# Sheet1.net
KiCad netlist of a schematic drawn in Altium Designer
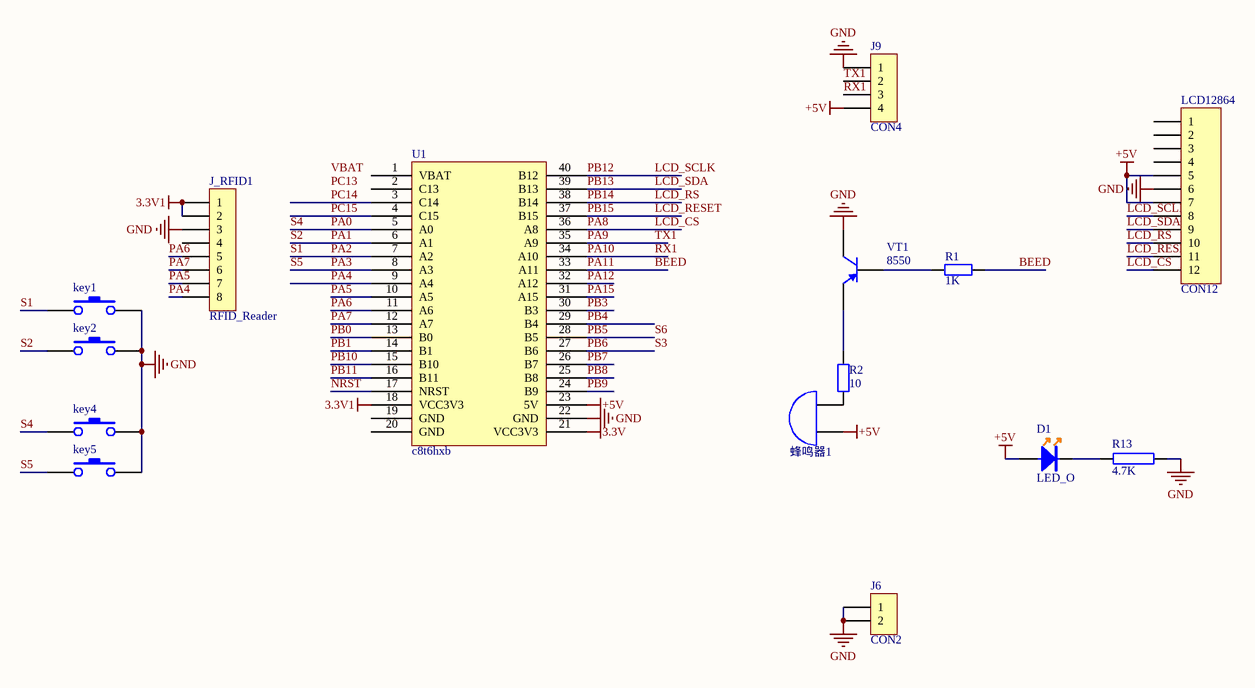
[diagram p0: Sheet1.SchDoc]

(export (version "E")
  (design (tool "Eeschema 10.0.6"))
  (components
    (comp (ref "D1") (value "LED_O") (footprint "D0805") (libsource (lib "Diode二极管") (part "LED_O")))
    (comp (ref "J6")
      (value "CON2")
      (footprint "sip-2")
      (description "Connector")
      (libsource (lib "接口") (part "CON2"))
    )
    (comp (ref "J9")
      (value "CON4")
      (footprint "sip-4")
      (description "Connector")
      (libsource (lib "接口") (part "CON4"))
    )
    (comp (ref "J_RFID1")
      (value "RFID_Reader")
      (footprint "SIP-8")
      (description "Connector")
      (libsource (lib "Plugs插头") (part "CON8"))
    )
    (comp (ref "key1") (value "~") (footprint "SW_SMD_P2") (libsource (lib "Switch开关") (part "SW-PB")))
    (comp (ref "key2") (value "~") (footprint "SW_SMD_P2") (libsource (lib "Switch开关") (part "SW-PB")))
    (comp (ref "key4") (value "~") (footprint "SW_SMD_P2") (libsource (lib "Switch开关") (part "SW-PB")))
    (comp (ref "key5") (value "~") (footprint "SW_SMD_P2") (libsource (lib "Switch开关") (part "SW-PB")))
    (comp (ref "LCD12864")
      (value "CON12")
      (footprint "sip-12")
      (description "Connector")
      (libsource (lib "接口") (part "CON12"))
    )
    (comp (ref "R1")
      (value "1K")
      (footprint "0805")
      (fields (field (name "Comment") "Res"))
      (libsource (lib "") (part "Res_1"))
    )
    (comp (ref "R2")
      (value "10")
      (footprint "0805")
      (fields (field (name "Comment") "Res"))
      (libsource (lib "MY") (part "Res"))
    )
    (comp (ref "R13") (value "4.7K") (footprint "0805") (libsource (lib "Resistance电阻") (part "RES")))
    (comp (ref "U1") (value "c8t6hxb") (footprint "48P") (libsource (lib "STM32F103C8T6") (part "c8t6hxb")))
    (comp (ref "VT1") (value "8550") (footprint "SOT-23") (libsource (lib "MY") (part "8550")))
    (comp (ref "蜂鸣器1") (value "蜂鸣器") (footprint "DB") (libsource (lib "MY") (part "蜂鸣器")))
  )
  (nets
    (net (code "1") (name "+5V") (class "Default")
      (node (ref "D1") (pin "1") (pinfunction "1_1") (pintype "passive"))
      (node (ref "J9") (pin "4") (pinfunction "4_4") (pintype "passive"))
      (node (ref "LCD12864") (pin "5") (pinfunction "5_5") (pintype "passive"))
      (node (ref "LCD12864") (pin "7") (pinfunction "7_7") (pintype "passive"))
      (node (ref "U1") (pin "23") (pinfunction "5V_23") (pintype "passive"))
      (node (ref "蜂鸣器1") (pin "1") (pinfunction "A_1") (pintype "passive"))
    )
    (net (code "2") (name "/BEED") (class "Default")
      (node (ref "R1") (pin "2") (pinfunction "2_2") (pintype "passive"))
      (node (ref "U1") (pin "33") (pinfunction "A11_33") (pintype "passive"))
    )
    (net (code "3") (name "/LCD_CS") (class "Default")
      (node (ref "LCD12864") (pin "12") (pinfunction "12_12") (pintype "passive"))
      (node (ref "U1") (pin "36") (pinfunction "A8_36") (pintype "passive"))
    )
    (net (code "4") (name "/LCD_RESET") (class "Default")
      (node (ref "LCD12864") (pin "11") (pinfunction "11_11") (pintype "passive"))
      (node (ref "U1") (pin "37") (pinfunction "B15_37") (pintype "passive"))
    )
    (net (code "5") (name "/LCD_RS") (class "Default")
      (node (ref "LCD12864") (pin "10") (pinfunction "10_10") (pintype "passive"))
      (node (ref "U1") (pin "38") (pinfunction "B14_38") (pintype "passive"))
    )
    (net (code "6") (name "/LCD_SCLK") (class "Default")
      (node (ref "LCD12864") (pin "8") (pinfunction "8_8") (pintype "passive"))
      (node (ref "U1") (pin "40") (pinfunction "B12_40") (pintype "passive"))
    )
    (net (code "7") (name "/LCD_SDA") (class "Default")
      (node (ref "LCD12864") (pin "9") (pinfunction "9_9") (pintype "passive"))
      (node (ref "U1") (pin "39") (pinfunction "B13_39") (pintype "passive"))
    )
    (net (code "8") (name "/NRST") (class "Default")
      (node (ref "U1") (pin "17") (pinfunction "NRST_17") (pintype "passive"))
    )
    (net (code "9") (name "/PA0") (class "Default")
      (node (ref "U1") (pin "5") (pinfunction "A0_5") (pintype "passive"))
      (node (ref "key4") (pin "1") (pinfunction "1_1") (pintype "passive"))
    )
    (net (code "10") (name "/PA1") (class "Default")
      (node (ref "U1") (pin "6") (pinfunction "A1_6") (pintype "passive"))
      (node (ref "key2") (pin "1") (pinfunction "1_1") (pintype "passive"))
    )
    (net (code "11") (name "/PA2") (class "Default")
      (node (ref "U1") (pin "7") (pinfunction "A2_7") (pintype "passive"))
      (node (ref "key1") (pin "1") (pinfunction "1_1") (pintype "passive"))
    )
    (net (code "12") (name "/PA3") (class "Default")
      (node (ref "U1") (pin "8") (pinfunction "A3_8") (pintype "passive"))
      (node (ref "key5") (pin "1") (pinfunction "1_1") (pintype "passive"))
    )
    (net (code "13") (name "/PA4") (class "Default")
      (node (ref "J_RFID1") (pin "8") (pinfunction "8_8") (pintype "passive"))
      (node (ref "U1") (pin "9") (pinfunction "A4_9") (pintype "passive"))
    )
    (net (code "14") (name "/PA5") (class "Default")
      (node (ref "J_RFID1") (pin "7") (pinfunction "7_7") (pintype "passive"))
      (node (ref "U1") (pin "10") (pinfunction "A5_10") (pintype "passive"))
    )
    (net (code "15") (name "/PA6") (class "Default")
      (node (ref "J_RFID1") (pin "5") (pinfunction "5_5") (pintype "passive"))
      (node (ref "U1") (pin "11") (pinfunction "A6_11") (pintype "passive"))
    )
    (net (code "16") (name "/PA7") (class "Default")
      (node (ref "J_RFID1") (pin "6") (pinfunction "6_6") (pintype "passive"))
      (node (ref "U1") (pin "12") (pinfunction "A7_12") (pintype "passive"))
    )
    (net (code "17") (name "/PA9") (class "Default")
      (node (ref "J9") (pin "2") (pinfunction "2_2") (pintype "passive"))
      (node (ref "U1") (pin "35") (pinfunction "A9_35") (pintype "passive"))
    )
    (net (code "18") (name "/PA10") (class "Default")
      (node (ref "J9") (pin "3") (pinfunction "3_3") (pintype "passive"))
      (node (ref "U1") (pin "34") (pinfunction "A10_34") (pintype "passive"))
    )
    (net (code "19") (name "/PA12") (class "Default")
      (node (ref "U1") (pin "32") (pinfunction "A12_32") (pintype "passive"))
    )
    (net (code "20") (name "/PA15") (class "Default")
      (node (ref "U1") (pin "31") (pinfunction "A15_31") (pintype "passive"))
    )
    (net (code "21") (name "/PB0") (class "Default")
      (node (ref "U1") (pin "13") (pinfunction "B0_13") (pintype "passive"))
    )
    (net (code "22") (name "/PB1") (class "Default")
      (node (ref "U1") (pin "14") (pinfunction "B1_14") (pintype "passive"))
    )
    (net (code "23") (name "/PB3") (class "Default")
      (node (ref "U1") (pin "30") (pinfunction "B3_30") (pintype "passive"))
    )
    (net (code "24") (name "/PB4") (class "Default")
      (node (ref "U1") (pin "29") (pinfunction "B4_29") (pintype "passive"))
    )
    (net (code "25") (name "/PB5") (class "Default")
      (node (ref "U1") (pin "28") (pinfunction "B5_28") (pintype "passive"))
    )
    (net (code "26") (name "/PB6") (class "Default")
      (node (ref "U1") (pin "27") (pinfunction "B6_27") (pintype "passive"))
    )
    (net (code "27") (name "/PB7") (class "Default")
      (node (ref "U1") (pin "26") (pinfunction "B7_26") (pintype "passive"))
    )
    (net (code "28") (name "/PB8") (class "Default")
      (node (ref "U1") (pin "25") (pinfunction "B8_25") (pintype "passive"))
    )
    (net (code "29") (name "/PB9") (class "Default")
      (node (ref "U1") (pin "24") (pinfunction "B9_24") (pintype "passive"))
    )
    (net (code "30") (name "/PB10") (class "Default")
      (node (ref "U1") (pin "15") (pinfunction "B10_15") (pintype "passive"))
    )
    (net (code "31") (name "/PB11") (class "Default")
      (node (ref "U1") (pin "16") (pinfunction "B11_16") (pintype "passive"))
    )
    (net (code "33") (name "/PC14") (class "Default")
      (node (ref "U1") (pin "3") (pinfunction "C14_3") (pintype "passive"))
    )
    (net (code "34") (name "/PC15") (class "Default")
      (node (ref "U1") (pin "4") (pinfunction "C15_4") (pintype "passive"))
    )
    (net (code "36") (name "3.3V") (class "Default")
      (node (ref "U1") (pin "21") (pinfunction "VCC3V3_21") (pintype "passive"))
    )
    (net (code "37") (name "3.3V1") (class "Default")
      (node (ref "J_RFID1") (pin "1") (pinfunction "1_1") (pintype "passive"))
      (node (ref "J_RFID1") (pin "2") (pinfunction "2_2") (pintype "passive"))
      (node (ref "U1") (pin "18") (pinfunction "VCC3V3_18") (pintype "passive"))
    )
    (net (code "38") (name "GND") (class "Default")
      (node (ref "J6") (pin "1") (pinfunction "1_1") (pintype "passive"))
      (node (ref "J6") (pin "2") (pinfunction "2_2") (pintype "passive"))
      (node (ref "J9") (pin "1") (pinfunction "1_1") (pintype "passive"))
      (node (ref "J_RFID1") (pin "3") (pinfunction "3_3") (pintype "passive"))
      (node (ref "LCD12864") (pin "6") (pinfunction "6_6") (pintype "passive"))
      (node (ref "R13") (pin "2") (pinfunction "2_2") (pintype "passive"))
      (node (ref "U1") (pin "22") (pinfunction "GND_22") (pintype "passive"))
      (node (ref "VT1") (pin "1") (pinfunction "C_1") (pintype "passive"))
      (node (ref "key1") (pin "2") (pinfunction "2_2") (pintype "passive"))
      (node (ref "key2") (pin "2") (pinfunction "2_2") (pintype "passive"))
      (node (ref "key4") (pin "2") (pinfunction "2_2") (pintype "passive"))
      (node (ref "key5") (pin "2") (pinfunction "2_2") (pintype "passive"))
    )
    (net (code "39") (name "Net-(D1-Pad2)") (class "Default")
      (node (ref "D1") (pin "2") (pinfunction "2_2") (pintype "passive"))
      (node (ref "R13") (pin "1") (pinfunction "1_1") (pintype "passive"))
    )
    (net (code "40") (name "Net-(VT1-B)") (class "Default")
      (node (ref "R1") (pin "1") (pinfunction "1_1") (pintype "passive"))
      (node (ref "VT1") (pin "2") (pinfunction "B_2") (pintype "passive"))
    )
    (net (code "41") (name "Net-(VT1-E)") (class "Default")
      (node (ref "R2") (pin "2") (pinfunction "2_2") (pintype "passive"))
      (node (ref "VT1") (pin "3") (pinfunction "E_3") (pintype "passive"))
    )
    (net (code "42") (name "Net-(蜂鸣器1-B)") (class "Default")
      (node (ref "R2") (pin "1") (pinfunction "1_1") (pintype "passive"))
      (node (ref "蜂鸣器1") (pin "2") (pinfunction "B_2") (pintype "passive"))
    )
    (net (code "43") (name "unconnected-(J_RFID1-Pad4)") (class "Default")
      (node (ref "J_RFID1") (pin "4") (pinfunction "4_4") (pintype "passive"))
    )
    (net (code "44") (name "unconnected-(LCD12864-Pad1)") (class "Default")
      (node (ref "LCD12864") (pin "1") (pinfunction "1_1") (pintype "passive"))
    )
    (net (code "45") (name "unconnected-(LCD12864-Pad2)") (class "Default")
      (node (ref "LCD12864") (pin "2") (pinfunction "2_2") (pintype "passive"))
    )
    (net (code "46") (name "unconnected-(LCD12864-Pad3)") (class "Default")
      (node (ref "LCD12864") (pin "3") (pinfunction "3_3") (pintype "passive"))
    )
    (net (code "47") (name "unconnected-(LCD12864-Pad4)") (class "Default")
      (node (ref "LCD12864") (pin "4") (pinfunction "4_4") (pintype "passive"))
    )
    (net (code "48") (name "unconnected-(U1-C13-Pad2)") (class "Default")
      (node (ref "U1") (pin "2") (pinfunction "C13_2") (pintype "passive"))
    )
    (net (code "49") (name "unconnected-(U1-GND-Pad19)") (class "Default")
      (node (ref "U1") (pin "19") (pinfunction "GND_19") (pintype "passive"))
    )
    (net (code "50") (name "unconnected-(U1-GND-Pad20)") (class "Default")
      (node (ref "U1") (pin "20") (pinfunction "GND_20") (pintype "passive"))
    )
    (net (code "51") (name "unconnected-(U1-VBAT-Pad1)") (class "Default")
      (node (ref "U1") (pin "1") (pinfunction "VBAT_1") (pintype "passive"))
    )
  )
)
